# AEON_Feeder_BeamBreak.net
KiCad netlist of a schematic drawn in Altium Designer
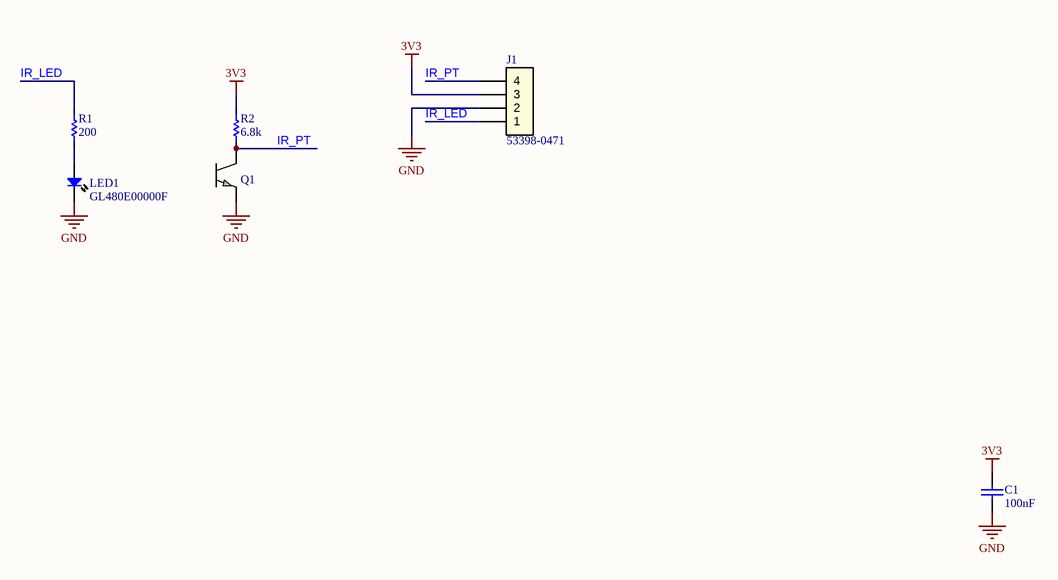
[diagram p0: AEON.Feeder.BeamBreak.SchDoc]

(export (version "E")
  (design (tool "Eeschema 10.0.6"))
  (components
    (comp (ref "C1")
      (value "100nF")
      (footprint "FP-GRM188-0_1-e0_2_0_5-IPC_B")
      (description "0.1µF ±10% 100V Ceramic Capacitor X7R 0603 (1608 Metric)")
      (fields (field (name "TOLERANCE") "10%") (field (name "VOLTAGE") "100V"))
      (libsource (lib "Sainsbury Wellcome Centre") (part "Cap"))
    )
    (comp (ref "J1")
      (value "53398-0471")
      (footprint "FP-533980471-MFG")
      (libsource (lib "Sainsbury Wellcome Centre") (part "Jack 4x1"))
    )
    (comp (ref "LED1")
      (value "GL480E00000F")
      (footprint "GL480_5.8mm")
      (description "EMITTER IR 950NM 50MA RADIAL")
      (fields (field (name "PARTNUMBER") "GL480E00000F"))
      (libsource (lib "Sainsbury Wellcome Centre") (part "LED-IR"))
    )
    (comp (ref "Q1")
      (value "PT480FE0000F")
      (footprint "PT480_5.8")
      (description "SHARP PT480FE0000F PHOTOTRANSISTOR")
      (libsource (lib "Sainsbury Wellcome Centre") (part "PT480"))
    )
    (comp (ref "R1")
      (value "200")
      (footprint "RES_ERA6A_0805_PAN")
      (description "RES 0805 200 Ohm 0.1% 1/8W ±10ppm/°C Thin Film")
      (fields (field (name "TOLERANCE") "0.1%") (field (name "PARTNUMBER") "RES 0805 200R 0.1% 125mW"))
      (libsource (lib "Sainsbury Wellcome Centre") (part "Res"))
    )
    (comp (ref "R2")
      (value "6.8k")
      (footprint "FP-CPF0603-IPC_B")
      (description "Surface Mount Resistor 6.8k Ohm 1/16 W 0.1% 0603 (1608 Metric)")
      (fields (field (name "TOLERANCE") "0.1%") (field (name "Comment") "R0603-6k8-1/16W-0.1%"))
      (libsource (lib "Sainsbury Wellcome Centre") (part "Res"))
    )
  )
  (nets
    (net (code "1") (name "/IR_LED") (class "Default")
      (node (ref "J1") (pin "1") (pinfunction "1_1") (pintype "passive"))
      (node (ref "R1") (pin "2") (pinfunction "2_2") (pintype "passive"))
    )
    (net (code "2") (name "/IR_PT") (class "Default")
      (node (ref "J1") (pin "4") (pinfunction "4_4") (pintype "passive"))
      (node (ref "Q1") (pin "2") (pinfunction "2_2") (pintype "passive"))
      (node (ref "R2") (pin "1") (pinfunction "1_1") (pintype "passive"))
    )
    (net (code "3") (name "3V3") (class "Default")
      (node (ref "C1") (pin "2") (pinfunction "2_2") (pintype "passive"))
      (node (ref "J1") (pin "3") (pinfunction "3_3") (pintype "passive"))
      (node (ref "R2") (pin "2") (pinfunction "2_2") (pintype "passive"))
    )
    (net (code "4") (name "GND") (class "Default")
      (node (ref "C1") (pin "1") (pinfunction "1_1") (pintype "passive"))
      (node (ref "J1") (pin "2") (pinfunction "2_2") (pintype "passive"))
      (node (ref "LED1") (pin "1") (pinfunction "C_1") (pintype "passive"))
      (node (ref "Q1") (pin "1") (pinfunction "1_1") (pintype "passive"))
    )
    (net (code "5") (name "Net-(LED1-A)") (class "Default")
      (node (ref "LED1") (pin "2") (pinfunction "A_2") (pintype "passive"))
      (node (ref "R1") (pin "1") (pinfunction "1_1") (pintype "passive"))
    )
  )
)
